# schema_breez.net
KiCad netlist of a schematic drawn in EAGLE
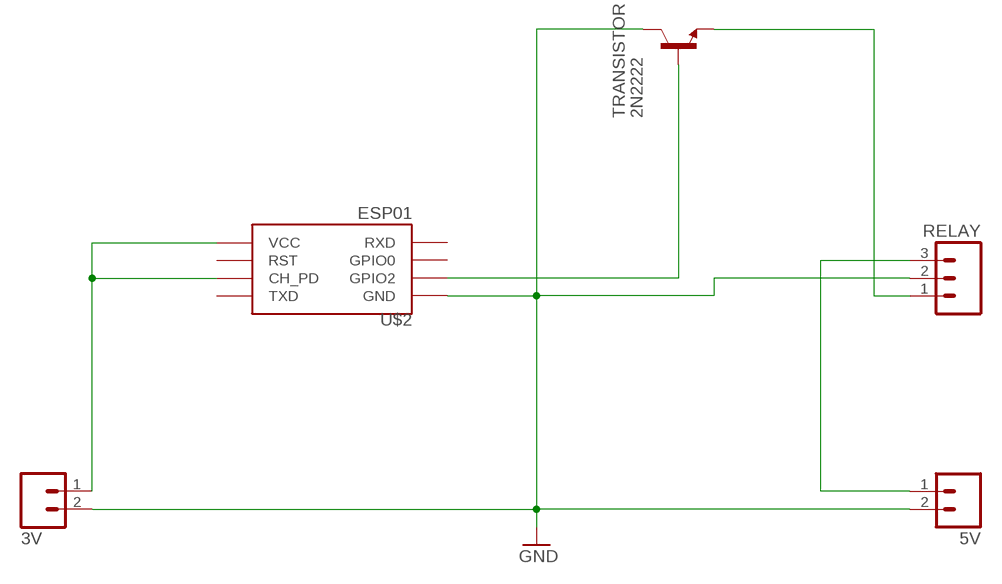
[diagram p0: schematic, sheet 1]

(export (version "E")
  (design (tool "Eeschema 10.0.6"))
  (components
    (comp (ref "3V")
      (value "M02")
      (footprint "eagle-import:02P")
      (libsource (lib "eagle-import") (part "M02"))
    )
    (comp (ref "5V")
      (value "M02")
      (footprint "eagle-import:02P")
      (libsource (lib "eagle-import") (part "M02"))
    )
    (comp (ref "RELAY")
      (value "M03")
      (footprint "eagle-import:03P")
      (libsource (lib "eagle-import") (part "M03"))
    )
    (comp (ref "TRANSISTOR")
      (value "2N2222")
      (footprint "eagle-import:TO18")
      (libsource (lib "eagle-import") (part "2N2222"))
    )
    (comp (ref "U$2")
      (value "ESP01")
      (footprint "eagle-import:ESP01")
      (libsource (lib "eagle-import") (part "ESP01"))
    )
  )
  (nets
    (net (code "1") (name "GND") (class "Default")
      (node (ref "3V") (pin "2") (pinfunction "2_2") (pintype "passive"))
      (node (ref "5V") (pin "2") (pinfunction "2_2") (pintype "passive"))
      (node (ref "RELAY") (pin "2") (pinfunction "2_2") (pintype "passive"))
      (node (ref "TRANSISTOR") (pin "3") (pinfunction "C_3") (pintype "passive"))
      (node (ref "U$2") (pin "GND") (pinfunction "GND_GND") (pintype "bidirectional"))
    )
    (net (code "2") (name "Net-(3V-Pad1)") (class "Default")
      (node (ref "3V") (pin "1") (pinfunction "1_1") (pintype "passive"))
      (node (ref "U$2") (pin "CH_PD") (pinfunction "CH_PD_CH_PD") (pintype "bidirectional"))
      (node (ref "U$2") (pin "VCC") (pinfunction "VCC_VCC") (pintype "bidirectional"))
    )
    (net (code "3") (name "Net-(5V-Pad1)") (class "Default")
      (node (ref "5V") (pin "1") (pinfunction "1_1") (pintype "passive"))
      (node (ref "RELAY") (pin "3") (pinfunction "3_3") (pintype "passive"))
    )
    (net (code "4") (name "Net-(TRANSISTOR-B)") (class "Default")
      (node (ref "TRANSISTOR") (pin "2") (pinfunction "B_2") (pintype "passive"))
      (node (ref "U$2") (pin "GPIO2") (pinfunction "GPIO2_GPIO2") (pintype "bidirectional"))
    )
    (net (code "5") (name "Net-(TRANSISTOR-E)") (class "Default")
      (node (ref "RELAY") (pin "1") (pinfunction "1_1") (pintype "passive"))
      (node (ref "TRANSISTOR") (pin "1") (pinfunction "E_1") (pintype "passive"))
    )
    (net (code "6") (name "unconnected-(U$2-PadGPIO0)") (class "Default")
      (node (ref "U$2") (pin "GPIO0") (pinfunction "GPIO0_GPIO0") (pintype "bidirectional"))
    )
    (net (code "7") (name "unconnected-(U$2-PadRST)") (class "Default")
      (node (ref "U$2") (pin "RST") (pinfunction "RST_RST") (pintype "bidirectional"))
    )
    (net (code "8") (name "unconnected-(U$2-RXD-PadRX)") (class "Default")
      (node (ref "U$2") (pin "RX") (pinfunction "RXD_RX") (pintype "bidirectional"))
    )
    (net (code "9") (name "unconnected-(U$2-TXD-PadTX)") (class "Default")
      (node (ref "U$2") (pin "TX") (pinfunction "TXD_TX") (pintype "bidirectional"))
    )
  )
)
